# CoffeeHeater.net
KiCad netlist of a schematic drawn in EAGLE
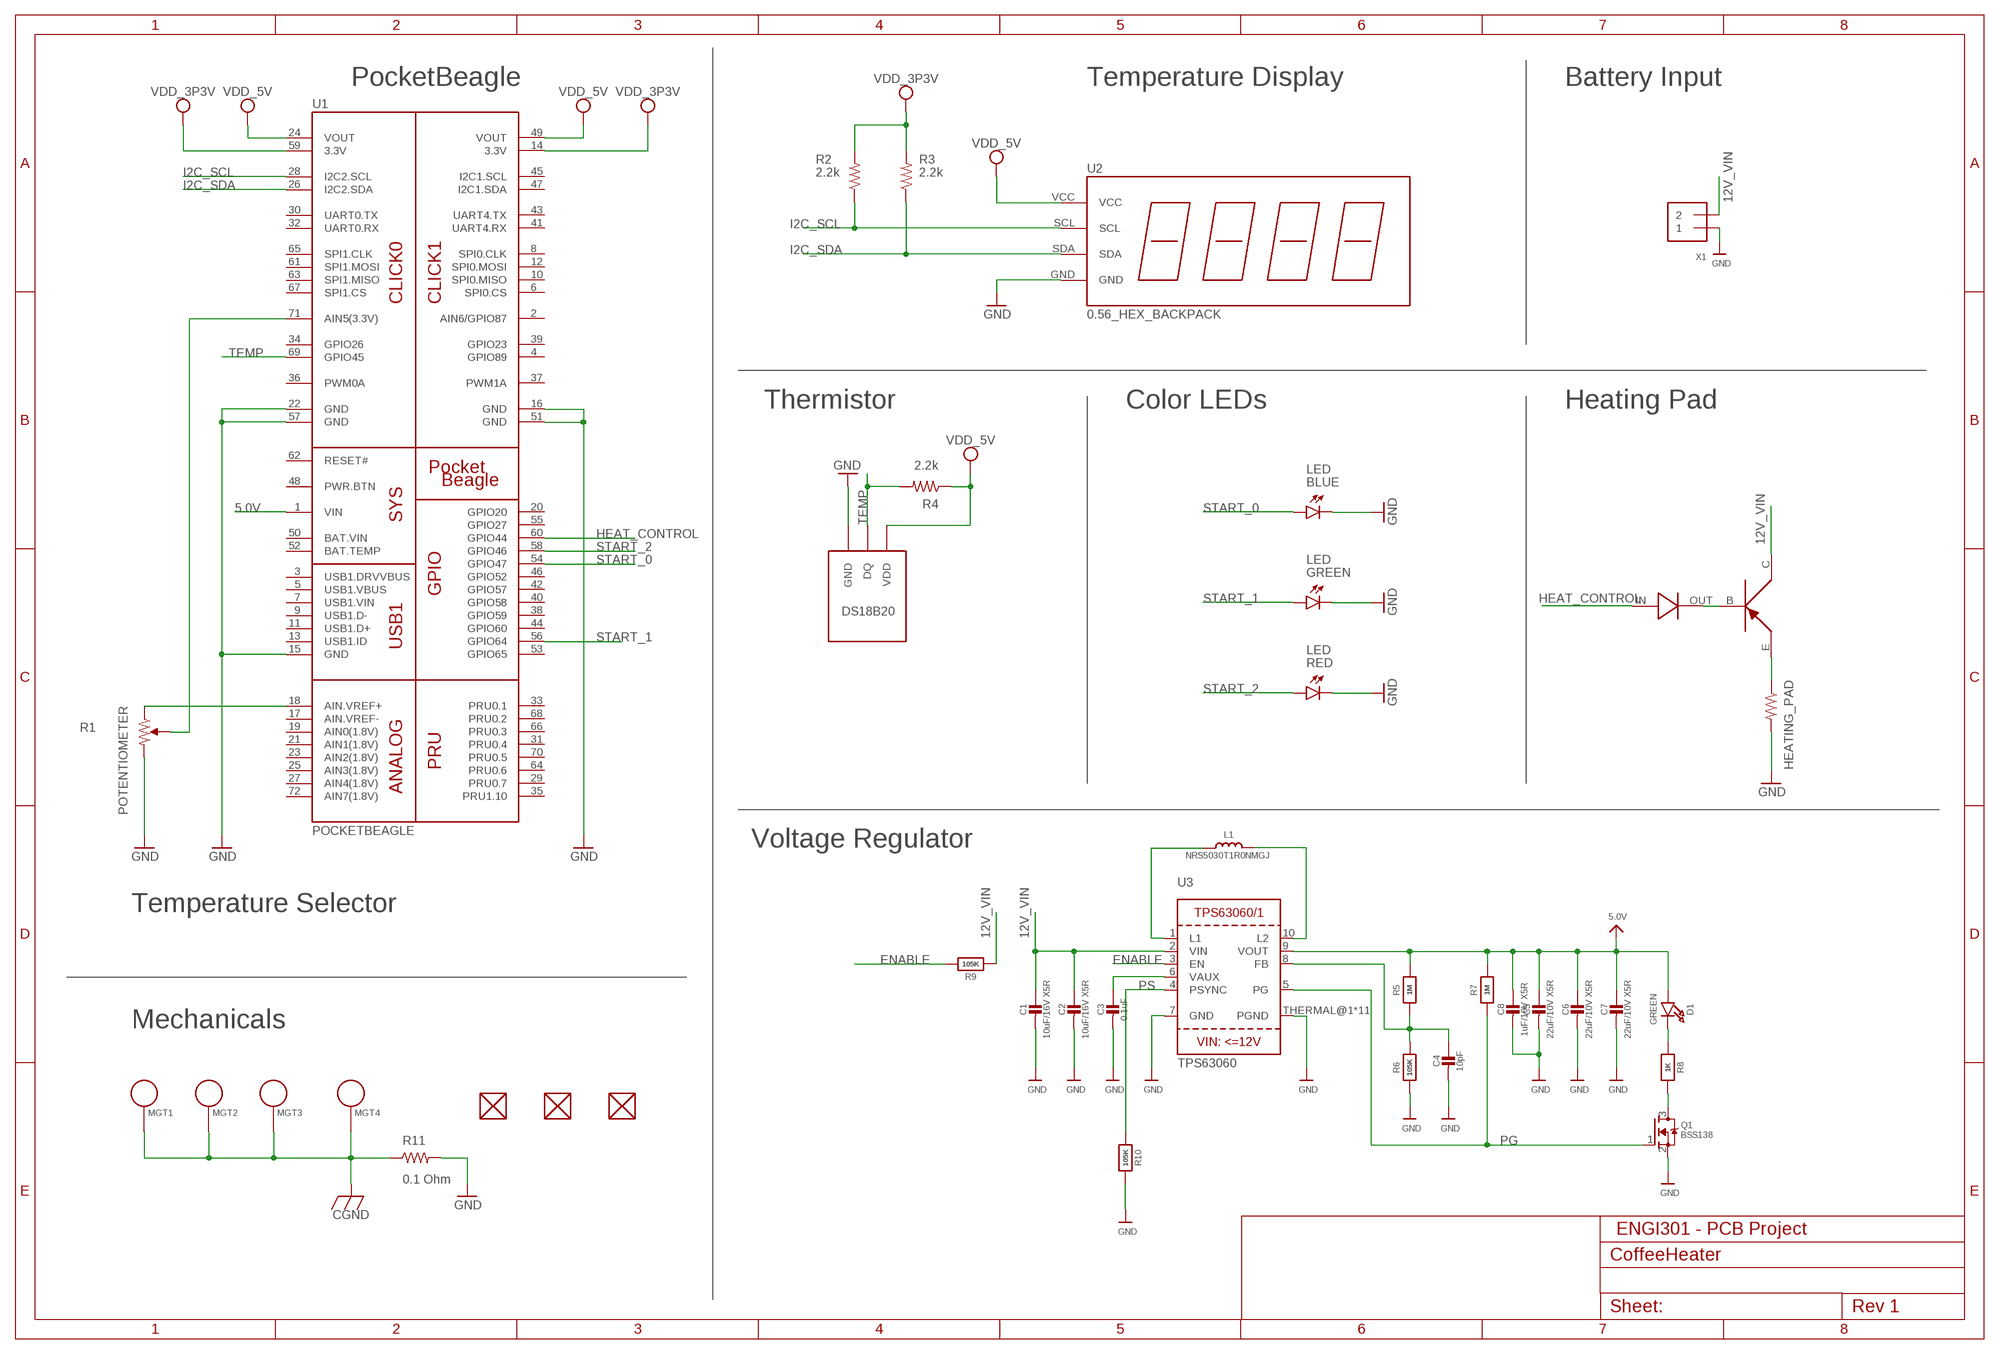
[diagram p0: schematic, sheet 1]

(export (version "E")
  (design (tool "Eeschema 10.0.6"))
  (components
    (comp (ref "BLUE")
      (value "LED")
      (footprint "eagle-import:EIA-STD")
      (libsource (lib "eagle-import") (part "LED"))
    )
    (comp (ref "C1")
      (value "10uF/16V X5R")
      (footprint "eagle-import:0805-NO")
      (libsource (lib "eagle-import") (part "CAP_CERAMIC0805-NOOUTLINE"))
    )
    (comp (ref "C2")
      (value "10uF/16V X5R")
      (footprint "eagle-import:0805-NO")
      (libsource (lib "eagle-import") (part "CAP_CERAMIC0805-NOOUTLINE"))
    )
    (comp (ref "C3")
      (value "0.1uF")
      (footprint "eagle-import:0805-NO")
      (libsource (lib "eagle-import") (part "CAP_CERAMIC0805-NOOUTLINE"))
    )
    (comp (ref "C4")
      (value "10pF")
      (footprint "eagle-import:0805-NO")
      (libsource (lib "eagle-import") (part "CAP_CERAMIC0805-NOOUTLINE"))
    )
    (comp (ref "C5")
      (value "22uF/10V X5R")
      (footprint "eagle-import:0805-NO")
      (libsource (lib "eagle-import") (part "CAP_CERAMIC0805-NOOUTLINE"))
    )
    (comp (ref "C6")
      (value "22uF/10V X5R")
      (footprint "eagle-import:0805-NO")
      (libsource (lib "eagle-import") (part "CAP_CERAMIC0805-NOOUTLINE"))
    )
    (comp (ref "C7")
      (value "22uF/10V X5R")
      (footprint "eagle-import:0805-NO")
      (libsource (lib "eagle-import") (part "CAP_CERAMIC0805-NOOUTLINE"))
    )
    (comp (ref "C8")
      (value "1uF/10V X5R")
      (footprint "eagle-import:0805-NO")
      (libsource (lib "eagle-import") (part "CAP_CERAMIC0805-NOOUTLINE"))
    )
    (comp (ref "D1")
      (value "GREEN")
      (footprint "eagle-import:CHIPLED_0805_NOOUTLINE")
      (libsource (lib "eagle-import") (part "LED0805_NOOUTLINE"))
    )
    (comp (ref "D2")
      (value "DIODE")
      (footprint "eagle-import:DIODE")
      (libsource (lib "eagle-import") (part "DIODE"))
    )
    (comp (ref "FUD1")
      (value "FIDUCIAL")
      (footprint "eagle-import:FIDUCIAL_40MIL")
      (libsource (lib "eagle-import") (part "FIDUCIAL"))
    )
    (comp (ref "FUD2")
      (value "FIDUCIAL")
      (footprint "eagle-import:FIDUCIAL_40MIL")
      (libsource (lib "eagle-import") (part "FIDUCIAL"))
    )
    (comp (ref "FUD3")
      (value "FIDUCIAL")
      (footprint "eagle-import:FIDUCIAL_40MIL")
      (libsource (lib "eagle-import") (part "FIDUCIAL"))
    )
    (comp (ref "GREEN")
      (value "LED")
      (footprint "eagle-import:EIA-STD")
      (libsource (lib "eagle-import") (part "LED"))
    )
    (comp (ref "H1")
      (value "HEATING_PAD")
      (footprint "eagle-import:HEATING_PAD")
      (libsource (lib "eagle-import") (part "HEATING_PAD"))
    )
    (comp (ref "L1")
      (value "NRS5030T1R0NMGJ")
      (footprint "eagle-import:INDUCTOR_5X5MM_TDK_VLC5045")
      (libsource (lib "eagle-import") (part "INDUCTORTDK_VLC5045"))
    )
    (comp (ref "MGT1")
      (value "MOUNTING_HOLE")
      (footprint "eagle-import:MOUNTING_HOLE")
      (libsource (lib "eagle-import") (part "MOUNTING_HOLE"))
    )
    (comp (ref "MGT2")
      (value "MOUNTING_HOLE")
      (footprint "eagle-import:MOUNTING_HOLE")
      (libsource (lib "eagle-import") (part "MOUNTING_HOLE"))
    )
    (comp (ref "MGT3")
      (value "MOUNTING_HOLE")
      (footprint "eagle-import:MOUNTING_HOLE")
      (libsource (lib "eagle-import") (part "MOUNTING_HOLE"))
    )
    (comp (ref "MGT4")
      (value "MOUNTING_HOLE")
      (footprint "eagle-import:MOUNTING_HOLE")
      (libsource (lib "eagle-import") (part "MOUNTING_HOLE"))
    )
    (comp (ref "Q1")
      (value "BSS138")
      (footprint "eagle-import:SOT23-WIDE")
      (libsource (lib "eagle-import") (part "MOSFET-NWIDE"))
    )
    (comp (ref "R1")
      (value "POTENTIOMETER")
      (footprint "eagle-import:POT-PO90S")
      (libsource (lib "eagle-import") (part "POTENTIOMETER"))
    )
    (comp (ref "R2")
      (value "2.2k")
      (footprint "eagle-import:R0603")
      (libsource (lib "eagle-import") (part "R_R0603"))
    )
    (comp (ref "R3")
      (value "2.2k")
      (footprint "eagle-import:R0603")
      (libsource (lib "eagle-import") (part "R_R0603"))
    )
    (comp (ref "R4")
      (value "2.2k")
      (footprint "eagle-import:R0603")
      (libsource (lib "eagle-import") (part "R_R0603"))
    )
    (comp (ref "R5")
      (value "1M")
      (footprint "eagle-import:0805-NO")
      (libsource (lib "eagle-import") (part "RESISTOR0805_NOOUTLINE"))
    )
    (comp (ref "R6")
      (value "105K")
      (footprint "eagle-import:0805-NO")
      (libsource (lib "eagle-import") (part "RESISTOR0805_NOOUTLINE"))
    )
    (comp (ref "R7")
      (value "1M")
      (footprint "eagle-import:0805-NO")
      (libsource (lib "eagle-import") (part "RESISTOR0805_NOOUTLINE"))
    )
    (comp (ref "R8")
      (value "1K")
      (footprint "eagle-import:0805-NO")
      (libsource (lib "eagle-import") (part "RESISTOR0805_NOOUTLINE"))
    )
    (comp (ref "R9")
      (value "105K")
      (footprint "eagle-import:0805-NO")
      (libsource (lib "eagle-import") (part "RESISTOR0805_NOOUTLINE"))
    )
    (comp (ref "R10")
      (value "105K")
      (footprint "eagle-import:0805-NO")
      (libsource (lib "eagle-import") (part "RESISTOR0805_NOOUTLINE"))
    )
    (comp (ref "R11")
      (value "0.1 Ohm")
      (footprint "eagle-import:R0805")
      (libsource (lib "eagle-import") (part "Whac-a-mole_R_R0805"))
    )
    (comp (ref "RED")
      (value "LED")
      (footprint "eagle-import:EIA-STD")
      (libsource (lib "eagle-import") (part "LED"))
    )
    (comp (ref "T1")
      (value "DS18B20_TEMP_SENSOR")
      (footprint "eagle-import:DS18B20_TEMP_SENSOR")
      (libsource (lib "eagle-import") (part "DS18B20_TEMP_SENSOR"))
    )
    (comp (ref "TR1")
      (value "TIP32C_TRANSISTOR")
      (footprint "eagle-import:TIP32C_TRANSISTOR")
      (libsource (lib "eagle-import") (part "TIP32C_TRANSISTOR"))
    )
    (comp (ref "U1")
      (value "POCKETBEAGLE")
      (footprint "eagle-import:POCKETBEAGLE")
      (libsource (lib "eagle-import") (part "POCKETBEAGLE"))
    )
    (comp (ref "U2")
      (value "0.56_HEX_BACKPACK")
      (footprint "eagle-import:0.56_HEX_BACKPACK")
      (libsource (lib "eagle-import") (part "0.56_HEX_BACKPACK"))
    )
    (comp (ref "U3")
      (value "TPS63060")
      (footprint "eagle-import:PWSON-N10")
      (libsource (lib "eagle-import") (part "VREG_TPS63060/1"))
    )
    (comp (ref "X1")
      (value "TERMBLOCK_1X2")
      (footprint "eagle-import:TERMBLOCK_1X2-3.5MM")
      (libsource (lib "eagle-import") (part "TERMBLOCK_1X2"))
    )
  )
  (nets
    (net (code "1") (name "/12V_VIN") (class "Default")
      (node (ref "C1") (pin "1") (pinfunction "1_1") (pintype "passive"))
      (node (ref "C2") (pin "1") (pinfunction "1_1") (pintype "passive"))
      (node (ref "R9") (pin "1") (pinfunction "1_1") (pintype "passive"))
      (node (ref "TR1") (pin "C") (pinfunction "C_C") (pintype "bidirectional"))
      (node (ref "U3") (pin "2") (pinfunction "VIN_2") (pintype "power_in"))
      (node (ref "X1") (pin "2") (pinfunction "2_2") (pintype "passive"))
    )
    (net (code "2") (name "/BAT.VIN") (class "Default")
      (node (ref "U1") (pin "50") (pinfunction "BAT.VIN_50") (pintype "power_in"))
    )
    (net (code "3") (name "/ENABLE") (class "Default")
      (node (ref "R9") (pin "2") (pinfunction "2_2") (pintype "passive"))
      (node (ref "U3") (pin "3") (pinfunction "EN_3") (pintype "input"))
    )
    (net (code "4") (name "/HEAT_CONTROL") (class "Default")
      (node (ref "D2") (pin "IN") (pinfunction "IN_IN") (pintype "bidirectional"))
      (node (ref "U1") (pin "60") (pinfunction "GPIO44_60") (pintype "bidirectional"))
    )
    (net (code "5") (name "/I2C_SCL") (class "Default")
      (node (ref "R2") (pin "1") (pinfunction "1_1") (pintype "passive"))
      (node (ref "U1") (pin "28") (pinfunction "I2C2.SCL_28") (pintype "bidirectional"))
      (node (ref "U2") (pin "SCL") (pinfunction "SCL_SCL") (pintype "bidirectional"))
    )
    (net (code "6") (name "/I2C_SDA") (class "Default")
      (node (ref "R3") (pin "1") (pinfunction "1_1") (pintype "passive"))
      (node (ref "U1") (pin "26") (pinfunction "I2C2.SDA_26") (pintype "bidirectional"))
      (node (ref "U2") (pin "SDA") (pinfunction "SDA_SDA") (pintype "bidirectional"))
    )
    (net (code "7") (name "/PG") (class "Default")
      (node (ref "Q1") (pin "1") (pinfunction "G_1") (pintype "bidirectional"))
      (node (ref "R7") (pin "1") (pinfunction "1_1") (pintype "passive"))
      (node (ref "U3") (pin "5") (pinfunction "PG_5") (pintype "open_collector"))
    )
    (net (code "8") (name "/PS") (class "Default")
      (node (ref "R10") (pin "1") (pinfunction "1_1") (pintype "passive"))
      (node (ref "U3") (pin "4") (pinfunction "PSYNC_4") (pintype "input"))
    )
    (net (code "9") (name "/START_0") (class "Default")
      (node (ref "BLUE") (pin "P$1") (pinfunction "A_P$1") (pintype "passive"))
      (node (ref "U1") (pin "54") (pinfunction "GPIO47_54") (pintype "bidirectional"))
    )
    (net (code "10") (name "/START_1") (class "Default")
      (node (ref "GREEN") (pin "P$1") (pinfunction "A_P$1") (pintype "passive"))
      (node (ref "U1") (pin "56") (pinfunction "GPIO64_56") (pintype "bidirectional"))
    )
    (net (code "11") (name "/START_2") (class "Default")
      (node (ref "RED") (pin "P$1") (pinfunction "A_P$1") (pintype "passive"))
      (node (ref "U1") (pin "58") (pinfunction "GPIO46_58") (pintype "bidirectional"))
    )
    (net (code "12") (name "/TEMP") (class "Default")
      (node (ref "R4") (pin "2") (pinfunction "2_2") (pintype "passive"))
      (node (ref "T1") (pin "DQ") (pinfunction "DQ_DQ") (pintype "bidirectional"))
      (node (ref "U1") (pin "69") (pinfunction "GPIO45_69") (pintype "bidirectional"))
    )
    (net (code "13") (name "5.0V") (class "Default")
      (node (ref "C5") (pin "1") (pinfunction "1_1") (pintype "passive"))
      (node (ref "C6") (pin "1") (pinfunction "1_1") (pintype "passive"))
      (node (ref "C7") (pin "1") (pinfunction "1_1") (pintype "passive"))
      (node (ref "C8") (pin "1") (pinfunction "1_1") (pintype "passive"))
      (node (ref "D1") (pin "A") (pinfunction "A_A") (pintype "passive"))
      (node (ref "R5") (pin "2") (pinfunction "2_2") (pintype "passive"))
      (node (ref "R7") (pin "2") (pinfunction "2_2") (pintype "passive"))
      (node (ref "U1") (pin "1") (pinfunction "VIN_1") (pintype "power_in"))
      (node (ref "U3") (pin "9") (pinfunction "VOUT_9") (pintype "power_in"))
    )
    (net (code "14") (name "CGND") (class "Default")
      (node (ref "MGT1") (pin "P$1") (pinfunction "P$1_P$1") (pintype "bidirectional"))
      (node (ref "MGT2") (pin "P$1") (pinfunction "P$1_P$1") (pintype "bidirectional"))
      (node (ref "MGT3") (pin "P$1") (pinfunction "P$1_P$1") (pintype "bidirectional"))
      (node (ref "MGT4") (pin "P$1") (pinfunction "P$1_P$1") (pintype "bidirectional"))
      (node (ref "R11") (pin "1") (pinfunction "1_1") (pintype "passive"))
    )
    (net (code "15") (name "GND") (class "Default")
      (node (ref "BLUE") (pin "P$2") (pinfunction "C_P$2") (pintype "passive"))
      (node (ref "C1") (pin "2") (pinfunction "2_2") (pintype "passive"))
      (node (ref "C2") (pin "2") (pinfunction "2_2") (pintype "passive"))
      (node (ref "C3") (pin "2") (pinfunction "2_2") (pintype "passive"))
      (node (ref "C4") (pin "2") (pinfunction "2_2") (pintype "passive"))
      (node (ref "C5") (pin "2") (pinfunction "2_2") (pintype "passive"))
      (node (ref "C6") (pin "2") (pinfunction "2_2") (pintype "passive"))
      (node (ref "C7") (pin "2") (pinfunction "2_2") (pintype "passive"))
      (node (ref "C8") (pin "2") (pinfunction "2_2") (pintype "passive"))
      (node (ref "GREEN") (pin "P$2") (pinfunction "C_P$2") (pintype "passive"))
      (node (ref "H1") (pin "GND") (pinfunction "2_GND") (pintype "passive"))
      (node (ref "Q1") (pin "2") (pinfunction "S_2") (pintype "bidirectional"))
      (node (ref "R1") (pin "CW") (pinfunction "CW_CW") (pintype "passive"))
      (node (ref "R10") (pin "2") (pinfunction "2_2") (pintype "passive"))
      (node (ref "R11") (pin "2") (pinfunction "2_2") (pintype "passive"))
      (node (ref "R6") (pin "1") (pinfunction "1_1") (pintype "passive"))
      (node (ref "RED") (pin "P$2") (pinfunction "C_P$2") (pintype "passive"))
      (node (ref "T1") (pin "GND") (pinfunction "GND_GND") (pintype "bidirectional"))
      (node (ref "U1") (pin "15") (pinfunction "GND_15") (pintype "bidirectional"))
      (node (ref "U1") (pin "16") (pinfunction "GND_16") (pintype "power_in"))
      (node (ref "U1") (pin "22") (pinfunction "GND_22") (pintype "power_in"))
      (node (ref "U1") (pin "51") (pinfunction "GND_51") (pintype "power_in"))
      (node (ref "U1") (pin "57") (pinfunction "GND_57") (pintype "power_in"))
      (node (ref "U2") (pin "GND") (pinfunction "GND_GND") (pintype "bidirectional"))
      (node (ref "U3") (pin "7") (pinfunction "GND_7") (pintype "power_in"))
      (node (ref "U3") (pin "THERMAL@1") (pinfunction "PGND_THERMAL@1") (pintype "power_in"))
      (node (ref "U3") (pin "THERMAL@10") (pinfunction "PGND_THERMAL@10") (pintype "power_in"))
      (node (ref "U3") (pin "THERMAL@11") (pinfunction "PGND_THERMAL@11") (pintype "power_in"))
      (node (ref "U3") (pin "THERMAL@12") (pinfunction "PGND_THERMAL@12") (pintype "power_in"))
      (node (ref "U3") (pin "THERMAL@13") (pinfunction "PGND_THERMAL@13") (pintype "power_in"))
      (node (ref "U3") (pin "THERMAL@14") (pinfunction "PGND_THERMAL@14") (pintype "power_in"))
      (node (ref "U3") (pin "THERMAL@5") (pinfunction "PGND_THERMAL@5") (pintype "power_in"))
      (node (ref "U3") (pin "THERMAL@6") (pinfunction "PGND_THERMAL@6") (pintype "power_in"))
      (node (ref "U3") (pin "THERMAL@7") (pinfunction "PGND_THERMAL@7") (pintype "power_in"))
      (node (ref "U3") (pin "THERMAL@8") (pinfunction "PGND_THERMAL@8") (pintype "power_in"))
      (node (ref "U3") (pin "THERMAL@9") (pinfunction "PGND_THERMAL@9") (pintype "power_in"))
      (node (ref "X1") (pin "1") (pinfunction "1_1") (pintype "passive"))
    )
    (net (code "16") (name "Net-(D1-PadC)") (class "Default")
      (node (ref "D1") (pin "C") (pinfunction "C_C") (pintype "passive"))
      (node (ref "R8") (pin "1") (pinfunction "1_1") (pintype "passive"))
    )
    (net (code "17") (name "Net-(D2-PadOUT)") (class "Default")
      (node (ref "D2") (pin "OUT") (pinfunction "OUT_OUT") (pintype "bidirectional"))
      (node (ref "TR1") (pin "B") (pinfunction "B_B") (pintype "bidirectional"))
    )
    (net (code "18") (name "Net-(H1-1)") (class "Default")
      (node (ref "H1") (pin "VDD") (pinfunction "1_VDD") (pintype "passive"))
      (node (ref "TR1") (pin "E") (pinfunction "E_E") (pintype "bidirectional"))
    )
    (net (code "19") (name "Net-(L1-1)") (class "Default")
      (node (ref "L1") (pin "P$1") (pinfunction "1_P$1") (pintype "passive"))
      (node (ref "U3") (pin "1") (pinfunction "L1_1") (pintype "input"))
    )
    (net (code "20") (name "Net-(L1-2)") (class "Default")
      (node (ref "L1") (pin "P$2") (pinfunction "2_P$2") (pintype "passive"))
      (node (ref "U3") (pin "10") (pinfunction "L2_10") (pintype "input"))
    )
    (net (code "21") (name "Net-(Q1-D)") (class "Default")
      (node (ref "Q1") (pin "3") (pinfunction "D_3") (pintype "bidirectional"))
      (node (ref "R8") (pin "2") (pinfunction "2_2") (pintype "passive"))
    )
    (net (code "22") (name "Net-(U1-AIN.VREF+)") (class "Default")
      (node (ref "R1") (pin "CCW") (pinfunction "CCW_CCW") (pintype "passive"))
      (node (ref "U1") (pin "18") (pinfunction "AIN.VREF+_18") (pintype "input"))
    )
    (net (code "23") (name "Net-(U1-AIN5(3.3V))") (class "Default")
      (node (ref "R1") (pin "S") (pinfunction "S_S") (pintype "bidirectional"))
      (node (ref "U1") (pin "71") (pinfunction "AIN5(3.3V)_71") (pintype "bidirectional"))
    )
    (net (code "24") (name "Net-(U3-FB)") (class "Default")
      (node (ref "C4") (pin "1") (pinfunction "1_1") (pintype "passive"))
      (node (ref "R5") (pin "1") (pinfunction "1_1") (pintype "passive"))
      (node (ref "R6") (pin "2") (pinfunction "2_2") (pintype "passive"))
      (node (ref "U3") (pin "8") (pinfunction "FB_8") (pintype "input"))
    )
    (net (code "25") (name "Net-(U3-VAUX)") (class "Default")
      (node (ref "C3") (pin "1") (pinfunction "1_1") (pintype "passive"))
      (node (ref "U3") (pin "6") (pinfunction "VAUX_6") (pintype "passive"))
    )
    (net (code "26") (name "VDD_3P3V") (class "Default")
      (node (ref "R2") (pin "2") (pinfunction "2_2") (pintype "passive"))
      (node (ref "R3") (pin "2") (pinfunction "2_2") (pintype "passive"))
      (node (ref "U1") (pin "14") (pinfunction "3.3V_14") (pintype "power_in"))
      (node (ref "U1") (pin "59") (pinfunction "3.3V_59") (pintype "power_in"))
    )
    (net (code "27") (name "VDD_5V") (class "Default")
      (node (ref "R4") (pin "1") (pinfunction "1_1") (pintype "passive"))
      (node (ref "T1") (pin "VDD") (pinfunction "VDD_VDD") (pintype "bidirectional"))
      (node (ref "U1") (pin "24") (pinfunction "VOUT_24") (pintype "power_in"))
      (node (ref "U1") (pin "49") (pinfunction "VOUT_49") (pintype "power_in"))
      (node (ref "U2") (pin "VCC") (pinfunction "VCC_VCC") (pintype "power_in"))
    )
    (net (code "28") (name "unconnected-(FUD1-PadP$1)") (class "Default")
      (node (ref "FUD1") (pin "P$1") (pinfunction "P$1_P$1") (pintype "no_connect"))
    )
    (net (code "29") (name "unconnected-(FUD2-PadP$1)") (class "Default")
      (node (ref "FUD2") (pin "P$1") (pinfunction "P$1_P$1") (pintype "no_connect"))
    )
    (net (code "30") (name "unconnected-(FUD3-PadP$1)") (class "Default")
      (node (ref "FUD3") (pin "P$1") (pinfunction "P$1_P$1") (pintype "no_connect"))
    )
    (net (code "31") (name "unconnected-(U1-AIN.VREF--Pad17)") (class "Default")
      (node (ref "U1") (pin "17") (pinfunction "AIN.VREF-_17") (pintype "input"))
    )
    (net (code "32") (name "unconnected-(U1-AIN0(1.8V)-Pad19)") (class "Default")
      (node (ref "U1") (pin "19") (pinfunction "AIN0(1.8V)_19") (pintype "input"))
    )
    (net (code "33") (name "unconnected-(U1-AIN1(1.8V)-Pad21)") (class "Default")
      (node (ref "U1") (pin "21") (pinfunction "AIN1(1.8V)_21") (pintype "input"))
    )
    (net (code "34") (name "unconnected-(U1-AIN2(1.8V)-Pad23)") (class "Default")
      (node (ref "U1") (pin "23") (pinfunction "AIN2(1.8V)_23") (pintype "input"))
    )
    (net (code "35") (name "unconnected-(U1-AIN3(1.8V)-Pad25)") (class "Default")
      (node (ref "U1") (pin "25") (pinfunction "AIN3(1.8V)_25") (pintype "input"))
    )
    (net (code "36") (name "unconnected-(U1-AIN4(1.8V)-Pad27)") (class "Default")
      (node (ref "U1") (pin "27") (pinfunction "AIN4(1.8V)_27") (pintype "input"))
    )
    (net (code "37") (name "unconnected-(U1-AIN6{slash}GPIO87-Pad2)") (class "Default")
      (node (ref "U1") (pin "2") (pinfunction "AIN6/GPIO87_2") (pintype "bidirectional"))
    )
    (net (code "38") (name "unconnected-(U1-AIN7(1.8V)-Pad72)") (class "Default")
      (node (ref "U1") (pin "72") (pinfunction "AIN7(1.8V)_72") (pintype "input"))
    )
    (net (code "39") (name "unconnected-(U1-BAT.TEMP-Pad52)") (class "Default")
      (node (ref "U1") (pin "52") (pinfunction "BAT.TEMP_52") (pintype "input"))
    )
    (net (code "40") (name "unconnected-(U1-GPIO20-Pad20)") (class "Default")
      (node (ref "U1") (pin "20") (pinfunction "GPIO20_20") (pintype "bidirectional"))
    )
    (net (code "41") (name "unconnected-(U1-GPIO23-Pad39)") (class "Default")
      (node (ref "U1") (pin "39") (pinfunction "GPIO23_39") (pintype "bidirectional"))
    )
    (net (code "42") (name "unconnected-(U1-GPIO26-Pad34)") (class "Default")
      (node (ref "U1") (pin "34") (pinfunction "GPIO26_34") (pintype "bidirectional"))
    )
    (net (code "43") (name "unconnected-(U1-GPIO27-Pad55)") (class "Default")
      (node (ref "U1") (pin "55") (pinfunction "GPIO27_55") (pintype "bidirectional"))
    )
    (net (code "44") (name "unconnected-(U1-GPIO52-Pad46)") (class "Default")
      (node (ref "U1") (pin "46") (pinfunction "GPIO52_46") (pintype "bidirectional"))
    )
    (net (code "45") (name "unconnected-(U1-GPIO57-Pad42)") (class "Default")
      (node (ref "U1") (pin "42") (pinfunction "GPIO57_42") (pintype "bidirectional"))
    )
    (net (code "46") (name "unconnected-(U1-GPIO58-Pad40)") (class "Default")
      (node (ref "U1") (pin "40") (pinfunction "GPIO58_40") (pintype "bidirectional"))
    )
    (net (code "47") (name "unconnected-(U1-GPIO59-Pad38)") (class "Default")
      (node (ref "U1") (pin "38") (pinfunction "GPIO59_38") (pintype "bidirectional"))
    )
    (net (code "48") (name "unconnected-(U1-GPIO60-Pad44)") (class "Default")
      (node (ref "U1") (pin "44") (pinfunction "GPIO60_44") (pintype "bidirectional"))
    )
    (net (code "49") (name "unconnected-(U1-GPIO65-Pad53)") (class "Default")
      (node (ref "U1") (pin "53") (pinfunction "GPIO65_53") (pintype "bidirectional"))
    )
    (net (code "50") (name "unconnected-(U1-GPIO89-Pad4)") (class "Default")
      (node (ref "U1") (pin "4") (pinfunction "GPIO89_4") (pintype "bidirectional"))
    )
    (net (code "51") (name "unconnected-(U1-I2C1.SCL-Pad45)") (class "Default")
      (node (ref "U1") (pin "45") (pinfunction "I2C1.SCL_45") (pintype "bidirectional"))
    )
    (net (code "52") (name "unconnected-(U1-I2C1.SDA-Pad47)") (class "Default")
      (node (ref "U1") (pin "47") (pinfunction "I2C1.SDA_47") (pintype "bidirectional"))
    )
    (net (code "53") (name "unconnected-(U1-PRU0.1-Pad33)") (class "Default")
      (node (ref "U1") (pin "33") (pinfunction "PRU0.1_33") (pintype "bidirectional"))
    )
    (net (code "54") (name "unconnected-(U1-PRU0.2-Pad68)") (class "Default")
      (node (ref "U1") (pin "68") (pinfunction "PRU0.2_68") (pintype "bidirectional"))
    )
    (net (code "55") (name "unconnected-(U1-PRU0.3-Pad66)") (class "Default")
      (node (ref "U1") (pin "66") (pinfunction "PRU0.3_66") (pintype "bidirectional"))
    )
    (net (code "56") (name "unconnected-(U1-PRU0.4-Pad31)") (class "Default")
      (node (ref "U1") (pin "31") (pinfunction "PRU0.4_31") (pintype "bidirectional"))
    )
    (net (code "57") (name "unconnected-(U1-PRU0.5-Pad70)") (class "Default")
      (node (ref "U1") (pin "70") (pinfunction "PRU0.5_70") (pintype "bidirectional"))
    )
    (net (code "58") (name "unconnected-(U1-PRU0.6-Pad64)") (class "Default")
      (node (ref "U1") (pin "64") (pinfunction "PRU0.6_64") (pintype "bidirectional"))
    )
    (net (code "59") (name "unconnected-(U1-PRU0.7-Pad29)") (class "Default")
      (node (ref "U1") (pin "29") (pinfunction "PRU0.7_29") (pintype "bidirectional"))
    )
    (net (code "60") (name "unconnected-(U1-PRU1.10-Pad35)") (class "Default")
      (node (ref "U1") (pin "35") (pinfunction "PRU1.10_35") (pintype "bidirectional"))
    )
    (net (code "61") (name "unconnected-(U1-PWM0A-Pad36)") (class "Default")
      (node (ref "U1") (pin "36") (pinfunction "PWM0A_36") (pintype "bidirectional"))
    )
    (net (code "62") (name "unconnected-(U1-PWM1A-Pad37)") (class "Default")
      (node (ref "U1") (pin "37") (pinfunction "PWM1A_37") (pintype "bidirectional"))
    )
    (net (code "63") (name "unconnected-(U1-PWR.BTN-Pad48)") (class "Default")
      (node (ref "U1") (pin "48") (pinfunction "PWR.BTN_48") (pintype "input"))
    )
    (net (code "64") (name "unconnected-(U1-RESET#-Pad62)") (class "Default")
      (node (ref "U1") (pin "62") (pinfunction "RESET#_62") (pintype "input"))
    )
    (net (code "65") (name "unconnected-(U1-SPI0.CLK-Pad8)") (class "Default")
      (node (ref "U1") (pin "8") (pinfunction "SPI0.CLK_8") (pintype "bidirectional"))
    )
    (net (code "66") (name "unconnected-(U1-SPI0.CS-Pad6)") (class "Default")
      (node (ref "U1") (pin "6") (pinfunction "SPI0.CS_6") (pintype "bidirectional"))
    )
    (net (code "67") (name "unconnected-(U1-SPI0.MISO-Pad10)") (class "Default")
      (node (ref "U1") (pin "10") (pinfunction "SPI0.MISO_10") (pintype "bidirectional"))
    )
    (net (code "68") (name "unconnected-(U1-SPI0.MOSI-Pad12)") (class "Default")
      (node (ref "U1") (pin "12") (pinfunction "SPI0.MOSI_12") (pintype "bidirectional"))
    )
    (net (code "69") (name "unconnected-(U1-SPI1.CLK-Pad65)") (class "Default")
      (node (ref "U1") (pin "65") (pinfunction "SPI1.CLK_65") (pintype "bidirectional"))
    )
    (net (code "70") (name "unconnected-(U1-SPI1.CS-Pad67)") (class "Default")
      (node (ref "U1") (pin "67") (pinfunction "SPI1.CS_67") (pintype "bidirectional"))
    )
    (net (code "71") (name "unconnected-(U1-SPI1.MISO-Pad63)") (class "Default")
      (node (ref "U1") (pin "63") (pinfunction "SPI1.MISO_63") (pintype "bidirectional"))
    )
    (net (code "72") (name "unconnected-(U1-SPI1.MOSI-Pad61)") (class "Default")
      (node (ref "U1") (pin "61") (pinfunction "SPI1.MOSI_61") (pintype "bidirectional"))
    )
    (net (code "73") (name "unconnected-(U1-UART0.RX-Pad32)") (class "Default")
      (node (ref "U1") (pin "32") (pinfunction "UART0.RX_32") (pintype "bidirectional"))
    )
    (net (code "74") (name "unconnected-(U1-UART0.TX-Pad30)") (class "Default")
      (node (ref "U1") (pin "30") (pinfunction "UART0.TX_30") (pintype "bidirectional"))
    )
    (net (code "75") (name "unconnected-(U1-UART4.RX-Pad41)") (class "Default")
      (node (ref "U1") (pin "41") (pinfunction "UART4.RX_41") (pintype "bidirectional"))
    )
    (net (code "76") (name "unconnected-(U1-UART4.TX-Pad43)") (class "Default")
      (node (ref "U1") (pin "43") (pinfunction "UART4.TX_43") (pintype "bidirectional"))
    )
    (net (code "77") (name "unconnected-(U1-USB1.D+-Pad11)") (class "Default")
      (node (ref "U1") (pin "11") (pinfunction "USB1.D+_11") (pintype "bidirectional"))
    )
    (net (code "78") (name "unconnected-(U1-USB1.D--Pad9)") (class "Default")
      (node (ref "U1") (pin "9") (pinfunction "USB1.D-_9") (pintype "bidirectional"))
    )
    (net (code "79") (name "unconnected-(U1-USB1.DRVVBUS-Pad3)") (class "Default")
      (node (ref "U1") (pin "3") (pinfunction "USB1.DRVVBUS_3") (pintype "bidirectional"))
    )
    (net (code "80") (name "unconnected-(U1-USB1.ID-Pad13)") (class "Default")
      (node (ref "U1") (pin "13") (pinfunction "USB1.ID_13") (pintype "bidirectional"))
    )
    (net (code "81") (name "unconnected-(U1-USB1.VBUS-Pad5)") (class "Default")
      (node (ref "U1") (pin "5") (pinfunction "USB1.VBUS_5") (pintype "bidirectional"))
    )
    (net (code "82") (name "unconnected-(U1-USB1.VIN-Pad7)") (class "Default")
      (node (ref "U1") (pin "7") (pinfunction "USB1.VIN_7") (pintype "bidirectional"))
    )
  )
)
